# erilabor.net
KiCad netlist of a schematic drawn in EAGLE
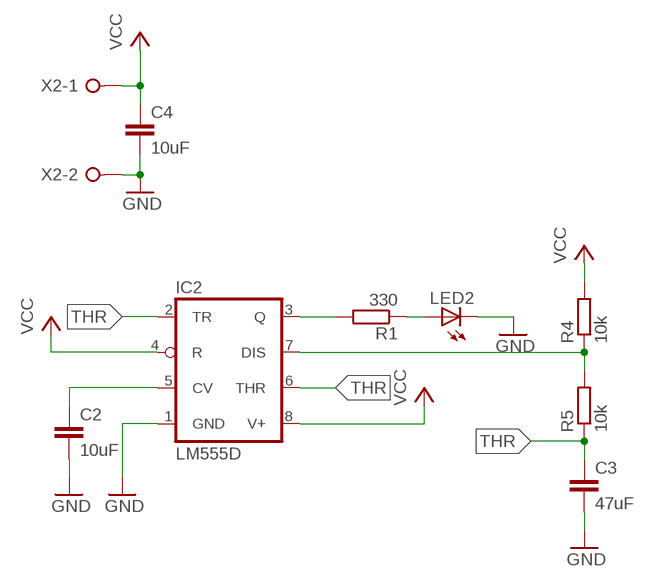
[diagram p0: schematic, sheet 1]

(export (version "E")
  (design (tool "Eeschema 10.0.6"))
  (components
    (comp (ref "C2")
      (value "10uF")
      (footprint "eagle-import:C0805K")
      (libsource (lib "eagle-import") (part "C-EUC0805K"))
    )
    (comp (ref "C3")
      (value "47uF")
      (footprint "eagle-import:C1210K")
      (libsource (lib "eagle-import") (part "C-EUC1210K"))
    )
    (comp (ref "C4")
      (value "10uF")
      (footprint "eagle-import:C0805K")
      (libsource (lib "eagle-import") (part "C-EUC0805K"))
    )
    (comp (ref "IC2")
      (value "LM555D")
      (footprint "eagle-import:SO08")
      (libsource (lib "eagle-import") (part "555DLM"))
    )
    (comp (ref "LED2")
      (value "LEDCHIP-LED0603")
      (footprint "eagle-import:CHIP-LED0603")
      (libsource (lib "eagle-import") (part "LEDCHIP-LED0603"))
    )
    (comp (ref "R1")
      (value "330")
      (footprint "eagle-import:R0603")
      (libsource (lib "eagle-import") (part "R-EU_R0603"))
    )
    (comp (ref "R4")
      (value "10k")
      (footprint "eagle-import:R0603")
      (libsource (lib "eagle-import") (part "R-EU_R0603"))
    )
    (comp (ref "R5")
      (value "10k")
      (footprint "eagle-import:R0603")
      (libsource (lib "eagle-import") (part "R-EU_R0603"))
    )
    (comp (ref "X2")
      (value "W237-2N")
      (footprint "eagle-import:W237-2N")
      (libsource (lib "eagle-import") (part "W237-2N"))
    )
  )
  (nets
    (net (code "1") (name "GND") (class "Default")
      (node (ref "C2") (pin "2") (pinfunction "2_2") (pintype "passive"))
      (node (ref "C3") (pin "2") (pinfunction "2_2") (pintype "passive"))
      (node (ref "C4") (pin "2") (pinfunction "2_2") (pintype "passive"))
      (node (ref "IC2") (pin "1") (pinfunction "GND_1") (pintype "power_in"))
      (node (ref "LED2") (pin "C") (pinfunction "C_C") (pintype "passive"))
      (node (ref "X2") (pin "2") (pinfunction "KL_2") (pintype "passive"))
    )
    (net (code "2") (name "Net-(IC2-CV)") (class "Default")
      (node (ref "C2") (pin "1") (pinfunction "1_1") (pintype "passive"))
      (node (ref "IC2") (pin "5") (pinfunction "CV_5") (pintype "input"))
    )
    (net (code "3") (name "Net-(IC2-DIS)") (class "Default")
      (node (ref "IC2") (pin "7") (pinfunction "DIS_7") (pintype "input"))
      (node (ref "R4") (pin "1") (pinfunction "1_1") (pintype "passive"))
      (node (ref "R5") (pin "2") (pinfunction "2_2") (pintype "passive"))
    )
    (net (code "4") (name "Net-(IC2-Q)") (class "Default")
      (node (ref "IC2") (pin "3") (pinfunction "Q_3") (pintype "output"))
      (node (ref "R1") (pin "2") (pinfunction "2_2") (pintype "passive"))
    )
    (net (code "5") (name "Net-(LED2-PadA)") (class "Default")
      (node (ref "LED2") (pin "A") (pinfunction "A_A") (pintype "passive"))
      (node (ref "R1") (pin "1") (pinfunction "1_1") (pintype "passive"))
    )
    (net (code "6") (name "THR") (class "Default")
      (node (ref "C3") (pin "1") (pinfunction "1_1") (pintype "passive"))
      (node (ref "IC2") (pin "2") (pinfunction "TR_2") (pintype "input"))
      (node (ref "IC2") (pin "6") (pinfunction "THR_6") (pintype "input"))
      (node (ref "R5") (pin "1") (pinfunction "1_1") (pintype "passive"))
    )
    (net (code "7") (name "VCC") (class "Default")
      (node (ref "C4") (pin "1") (pinfunction "1_1") (pintype "passive"))
      (node (ref "IC2") (pin "4") (pinfunction "R_4") (pintype "input"))
      (node (ref "IC2") (pin "8") (pinfunction "V+_8") (pintype "power_in"))
      (node (ref "R4") (pin "2") (pinfunction "2_2") (pintype "passive"))
      (node (ref "X2") (pin "1") (pinfunction "KL_1") (pintype "passive"))
    )
  )
)
